# DAC.net
KiCad netlist of a schematic drawn in Altium Designer
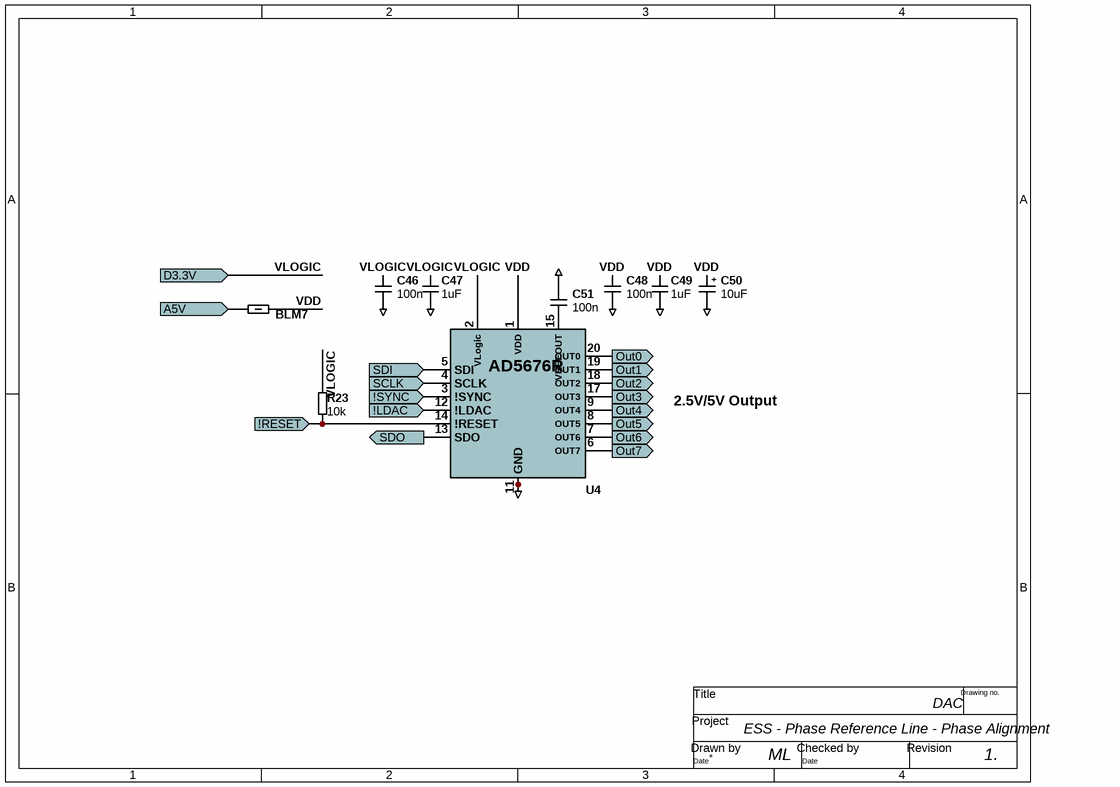
[diagram p0: DAC.SchDoc]

(export (version "E")
  (design (tool "Eeschema 10.0.6"))
  (components
    (comp (ref "BLM7")
      (value "120 Ohms @ 100MHz")
      (footprint "0402-Inductor")
      (description "120 Ohms @ 100MHz 1 Power, Signal Line Ferrite Bead 0402 (1005 Metric) 700mA 130mOhm")
      (libsource (lib "PRL_PDC") (part "BLM15AX121SZ1D"))
    )
    (comp (ref "C46")
      (value "100n")
      (footprint "0402-Capacitor")
      (description "Capacitor 0402")
      (fields (field (name "TOLERANCE") "±20%"))
      (libsource (lib "PRL_PDC") (part "C_0402"))
    )
    (comp (ref "C47")
      (value "1uF")
      (footprint "0805-Capacitor")
      (description "Capacitor 0805")
      (fields (field (name "TOLERANCE") "±20%"))
      (libsource (lib "PRL_PDC") (part "C_0805"))
    )
    (comp (ref "C48")
      (value "100n")
      (footprint "0402-Capacitor")
      (description "Capacitor 0402")
      (fields (field (name "TOLERANCE") "±20%"))
      (libsource (lib "PRL_PDC") (part "C_0402"))
    )
    (comp (ref "C49")
      (value "1uF")
      (footprint "0805-Capacitor")
      (description "Capacitor 0805")
      (fields (field (name "TOLERANCE") "±20%"))
      (libsource (lib "PRL_PDC") (part "C_0805"))
    )
    (comp (ref "C50")
      (value "10uF")
      (footprint "1206-cap_tant")
      (description "CAP TANT 10UF 10% 16V 1206")
      (libsource (lib "PRL_PDC") (part "C_10uF_Tant_16V_1206"))
    )
    (comp (ref "C51")
      (value "100n")
      (footprint "0402-Capacitor")
      (description "Capacitor 0402")
      (fields (field (name "TOLERANCE") "±20%"))
      (libsource (lib "PRL_PDC") (part "C_0402"))
    )
    (comp (ref "R23")
      (value "10k")
      (footprint "0402-RESISTOR")
      (description "Resistor 0402")
      (fields (field (name "TOLERANCE") "±1%"))
      (libsource (lib "PRL_PDC") (part "R_0402"))
    )
    (comp (ref "U4")
      (value "AD5676R")
      (footprint "LFCSP-20")
      (description "Octal, 16-Bit nanoDAC+ with 2 ppm/°C Reference, SPI Interface")
      (libsource (lib "PRL_PDC") (part "AD5676R"))
    )
  )
  (nets
    (net (code "1") (name "/!LDAC") (class "Default")
      (node (ref "U4") (pin "12") (pinfunction "!LDAC_12") (pintype "passive"))
    )
    (net (code "2") (name "/!RESET") (class "Default")
      (node (ref "R23") (pin "2") (pinfunction "2_2") (pintype "passive"))
      (node (ref "U4") (pin "14") (pinfunction "!RESET_14") (pintype "passive"))
    )
    (net (code "3") (name "/!SYNC") (class "Default")
      (node (ref "U4") (pin "3") (pinfunction "!SYNC_3") (pintype "passive"))
    )
    (net (code "4") (name "/A5V") (class "Default") (node (ref "BLM7") (pin "1") (pintype "passive")))
    (net (code "5") (name "/Out0") (class "Default")
      (node (ref "U4") (pin "20") (pinfunction "OUT0_20") (pintype "passive"))
    )
    (net (code "6") (name "/Out1") (class "Default")
      (node (ref "U4") (pin "19") (pinfunction "OUT1_19") (pintype "passive"))
    )
    (net (code "7") (name "/Out2") (class "Default")
      (node (ref "U4") (pin "18") (pinfunction "OUT2_18") (pintype "passive"))
    )
    (net (code "8") (name "/Out3") (class "Default")
      (node (ref "U4") (pin "17") (pinfunction "OUT3_17") (pintype "passive"))
    )
    (net (code "9") (name "/Out4") (class "Default")
      (node (ref "U4") (pin "9") (pinfunction "OUT4_9") (pintype "passive"))
    )
    (net (code "10") (name "/Out5") (class "Default")
      (node (ref "U4") (pin "8") (pinfunction "OUT5_8") (pintype "passive"))
    )
    (net (code "11") (name "/Out6") (class "Default")
      (node (ref "U4") (pin "7") (pinfunction "OUT6_7") (pintype "passive"))
    )
    (net (code "12") (name "/Out7") (class "Default")
      (node (ref "U4") (pin "6") (pinfunction "OUT7_6") (pintype "passive"))
    )
    (net (code "13") (name "/SCLK") (class "Default")
      (node (ref "U4") (pin "4") (pinfunction "SCLK_4") (pintype "passive"))
    )
    (net (code "14") (name "/SDI") (class "Default")
      (node (ref "U4") (pin "5") (pinfunction "SDI_5") (pintype "passive"))
    )
    (net (code "15") (name "/SDO") (class "Default")
      (node (ref "U4") (pin "13") (pinfunction "SDO_13") (pintype "passive"))
    )
    (net (code "16") (name "/VDD") (class "Default")
      (node (ref "BLM7") (pin "2") (pintype "passive"))
      (node (ref "C48") (pin "2") (pinfunction "2_2") (pintype "passive"))
      (node (ref "C49") (pin "1") (pinfunction "1_1") (pintype "passive"))
      (node (ref "C50") (pin "1") (pinfunction "+_1") (pintype "passive"))
      (node (ref "U4") (pin "1") (pinfunction "VDD_1") (pintype "passive"))
    )
    (net (code "17") (name "/VLOGIC") (class "Default")
      (node (ref "C46") (pin "2") (pinfunction "2_2") (pintype "passive"))
      (node (ref "C47") (pin "1") (pinfunction "1_1") (pintype "passive"))
      (node (ref "R23") (pin "1") (pinfunction "1_1") (pintype "passive"))
      (node (ref "U4") (pin "2") (pinfunction "VLogic_2") (pintype "passive"))
    )
    (net (code "18") (name "GND") (class "Default")
      (node (ref "C46") (pin "1") (pinfunction "1_1") (pintype "passive"))
      (node (ref "C47") (pin "2") (pinfunction "2_2") (pintype "passive"))
      (node (ref "C48") (pin "1") (pinfunction "1_1") (pintype "passive"))
      (node (ref "C49") (pin "2") (pinfunction "2_2") (pintype "passive"))
      (node (ref "C50") (pin "2") (pinfunction "-_2") (pintype "passive"))
      (node (ref "C51") (pin "2") (pinfunction "2_2") (pintype "passive"))
      (node (ref "U4") (pin "11") (pinfunction "GND_11") (pintype "passive"))
      (node (ref "U4") (pin "EP") (pinfunction "EP_EP") (pintype "passive"))
    )
    (net (code "19") (name "Net-(U4-VREFOUT)") (class "Default")
      (node (ref "C51") (pin "1") (pinfunction "1_1") (pintype "passive"))
      (node (ref "U4") (pin "15") (pinfunction "VREFOUT_15") (pintype "passive"))
    )
    (net (code "20") (name "unconnected-(U4-NC-Pad10)") (class "Default")
      (node (ref "U4") (pin "10") (pinfunction "NC_10") (pintype "passive"))
    )
    (net (code "21") (name "unconnected-(U4-NC-Pad16)") (class "Default")
      (node (ref "U4") (pin "16") (pinfunction "NC_16") (pintype "passive"))
    )
  )
)
